# ArduinoMicroPrinter.net
KiCad netlist of a schematic drawn in EAGLE
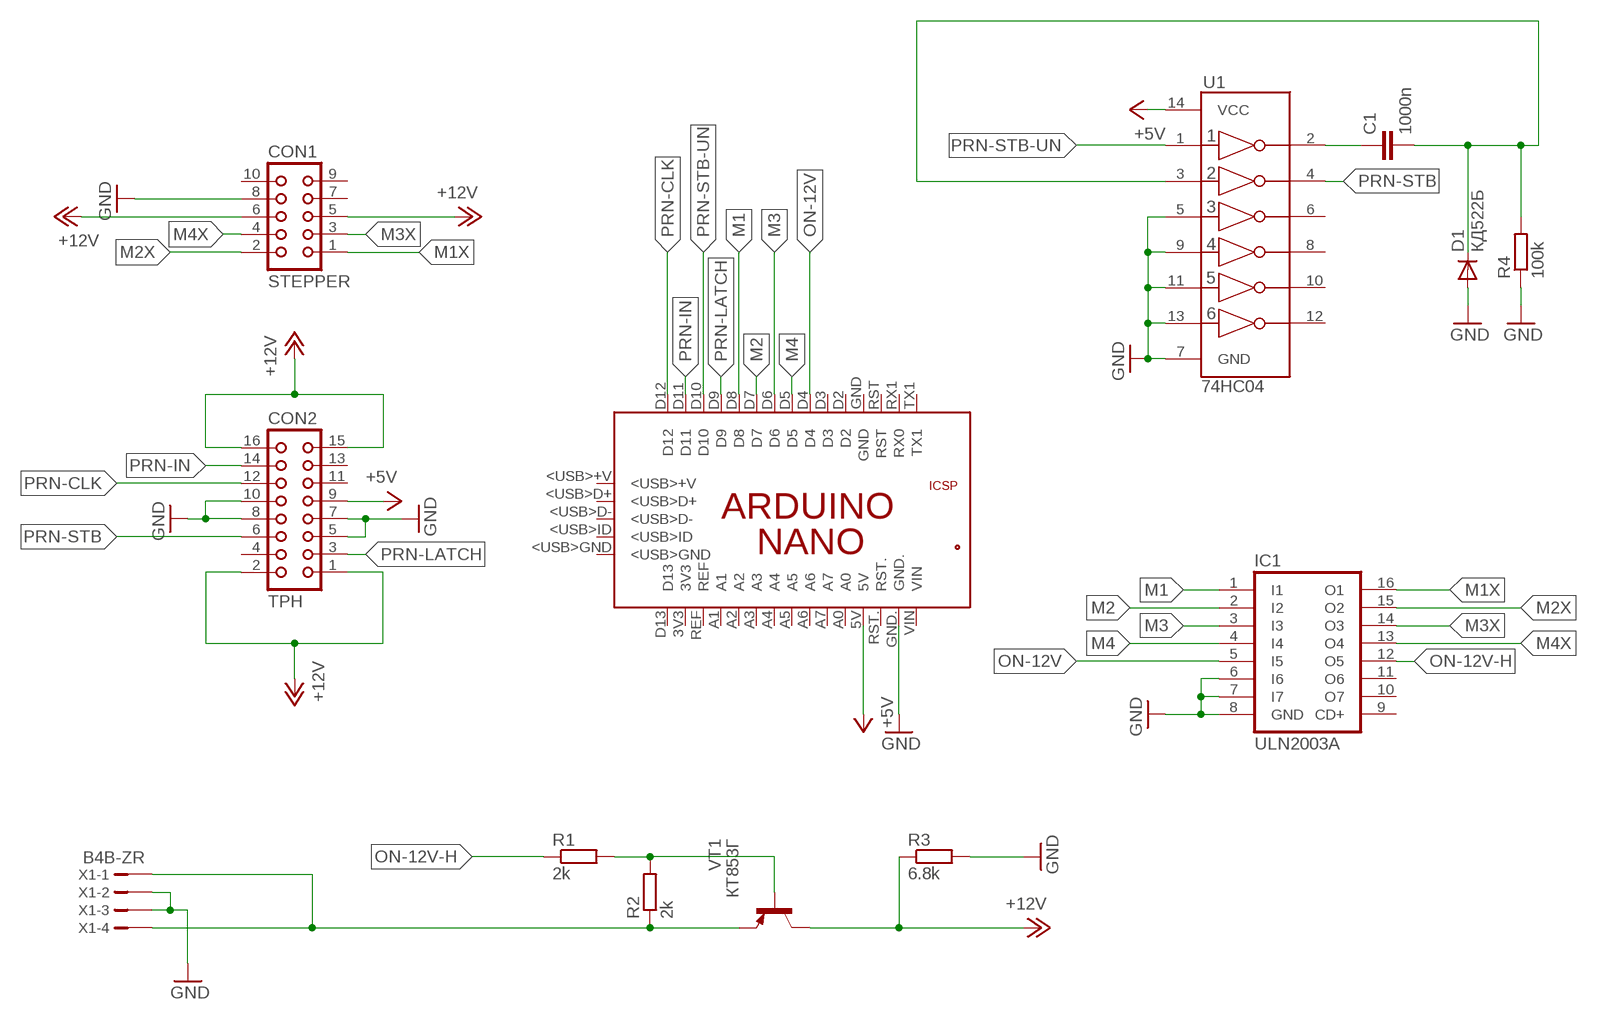
[diagram p0: schematic, sheet 1]

(export (version "E")
  (design (tool "Eeschema 10.0.6"))
  (components
    (comp (ref "C1")
      (value "1000n")
      (footprint "eagle-import:C075-032X103")
      (libsource (lib "eagle-import") (part "C-EU075-032X103"))
    )
    (comp (ref "CON1")
      (value "STEPPER")
      (footprint "eagle-import:CON10")
      (fields
        (field (name "MF") "TE CONNECTIVITY / AMP")
        (field (name "MPN") "0-281273-1")
        (field (name "OC_FARNELL") "3816278")
      )
      (libsource (lib "eagle-import") (part "CON10"))
    )
    (comp (ref "CON2")
      (value "TPH")
      (footprint "eagle-import:CON16")
      (fields
        (field (name "MF") "TE CONNECTIVITY / AMP")
        (field (name "MPN") "1-1634688-0")
        (field (name "OC_FARNELL") "8395918")
      )
      (libsource (lib "eagle-import") (part "CON16"))
    )
    (comp (ref "D1")
      (value "КД522Б")
      (footprint "eagle-import:DO35-10")
      (libsource (lib "eagle-import") (part "1N4148DO35-10"))
    )
    (comp (ref "IC1")
      (value "ULN2003A")
      (footprint "eagle-import:DIL16")
      (libsource (lib "eagle-import") (part "ULN2003AN"))
    )
    (comp (ref "PCB1")
      (value "ARDUINO_NANO")
      (footprint "eagle-import:ARDUINO_NANO")
      (fields (field (name "MF") "ARDUINO") (field (name "MPN") "A000005"))
      (libsource (lib "eagle-import") (part "ARDUINO_NANO"))
    )
    (comp (ref "R1")
      (value "2k")
      (footprint "eagle-import:0207_12")
      (libsource (lib "eagle-import") (part "R-EU_0207/12"))
    )
    (comp (ref "R2")
      (value "2k")
      (footprint "eagle-import:0207_12")
      (libsource (lib "eagle-import") (part "R-EU_0207/12"))
    )
    (comp (ref "R3")
      (value "6.8k")
      (footprint "eagle-import:0207_12")
      (libsource (lib "eagle-import") (part "R-EU_0207/12"))
    )
    (comp (ref "R4")
      (value "100k")
      (footprint "eagle-import:0309_12")
      (libsource (lib "eagle-import") (part "R-EU_0309/12"))
    )
    (comp (ref "U1")
      (value "74HC04")
      (footprint "eagle-import:DIL14")
      (libsource (lib "eagle-import") (part "74HC04_HEX_INVERTER"))
    )
    (comp (ref "VT1")
      (value "КТ853Г")
      (footprint "eagle-import:TO220")
      (libsource (lib "eagle-import") (part "TIP30"))
    )
    (comp (ref "X1")
      (value "B4B-ZR")
      (footprint "eagle-import:B4B-ZR")
      (fields (field (name "MF") "FARNELL") (field (name "MPN") "B4B-ZR(LF)(SN)"))
      (libsource (lib "eagle-import") (part "?4B-ZRB"))
    )
  )
  (nets
    (net (code "1") (name "+5V") (class "Default")
      (node (ref "CON2") (pin "9") (pinfunction "9_9") (pintype "passive"))
      (node (ref "PCB1") (pin "5V") (pinfunction "5V_5V") (pintype "bidirectional"))
      (node (ref "U1") (pin "14") (pinfunction "VCC_14") (pintype "power_in"))
    )
    (net (code "2") (name "+12V") (class "Default")
      (node (ref "CON1") (pin "5") (pinfunction "5_5") (pintype "passive"))
      (node (ref "CON1") (pin "6") (pinfunction "6_6") (pintype "passive"))
      (node (ref "CON2") (pin "1") (pinfunction "1_1") (pintype "passive"))
      (node (ref "CON2") (pin "15") (pinfunction "15_15") (pintype "passive"))
      (node (ref "CON2") (pin "16") (pinfunction "16_16") (pintype "passive"))
      (node (ref "CON2") (pin "2") (pinfunction "2_2") (pintype "passive"))
      (node (ref "R3") (pin "1") (pinfunction "1_1") (pintype "passive"))
      (node (ref "VT1") (pin "2") (pinfunction "C_2") (pintype "passive"))
    )
    (net (code "3") (name "GND") (class "Default")
      (node (ref "CON1") (pin "8") (pinfunction "8_8") (pintype "passive"))
      (node (ref "CON2") (pin "10") (pinfunction "10_10") (pintype "passive"))
      (node (ref "CON2") (pin "5") (pinfunction "5_5") (pintype "passive"))
      (node (ref "CON2") (pin "7") (pinfunction "7_7") (pintype "passive"))
      (node (ref "CON2") (pin "8") (pinfunction "8_8") (pintype "passive"))
      (node (ref "D1") (pin "A") (pinfunction "A_A") (pintype "passive"))
      (node (ref "IC1") (pin "6") (pinfunction "I6_6") (pintype "input"))
      (node (ref "IC1") (pin "7") (pinfunction "I7_7") (pintype "input"))
      (node (ref "IC1") (pin "8") (pinfunction "GND_8") (pintype "power_in"))
      (node (ref "PCB1") (pin "GND.") (pinfunction "GND._GND.") (pintype "bidirectional"))
      (node (ref "R3") (pin "2") (pinfunction "2_2") (pintype "passive"))
      (node (ref "R4") (pin "1") (pinfunction "1_1") (pintype "passive"))
      (node (ref "U1") (pin "11") (pinfunction "5A_11") (pintype "input"))
      (node (ref "U1") (pin "13") (pinfunction "6A_13") (pintype "input"))
      (node (ref "U1") (pin "5") (pinfunction "3A_5") (pintype "input"))
      (node (ref "U1") (pin "7") (pinfunction "GND_7") (pintype "power_in"))
      (node (ref "U1") (pin "9") (pinfunction "4A_9") (pintype "input"))
      (node (ref "X1") (pin "2") (pinfunction "1_2") (pintype "passive"))
      (node (ref "X1") (pin "3") (pinfunction "1_3") (pintype "passive"))
    )
    (net (code "4") (name "M1") (class "Default")
      (node (ref "IC1") (pin "1") (pinfunction "I1_1") (pintype "input"))
      (node (ref "PCB1") (pin "D8") (pinfunction "D8_D8") (pintype "bidirectional"))
    )
    (net (code "5") (name "M1X") (class "Default")
      (node (ref "CON1") (pin "1") (pinfunction "1_1") (pintype "passive"))
      (node (ref "IC1") (pin "16") (pinfunction "O1_16") (pintype "open_collector"))
    )
    (net (code "6") (name "M2") (class "Default")
      (node (ref "IC1") (pin "2") (pinfunction "I2_2") (pintype "input"))
      (node (ref "PCB1") (pin "D7") (pinfunction "D7_D7") (pintype "bidirectional"))
    )
    (net (code "7") (name "M2X") (class "Default")
      (node (ref "CON1") (pin "2") (pinfunction "2_2") (pintype "passive"))
      (node (ref "IC1") (pin "15") (pinfunction "O2_15") (pintype "open_collector"))
    )
    (net (code "8") (name "M3") (class "Default")
      (node (ref "IC1") (pin "3") (pinfunction "I3_3") (pintype "input"))
      (node (ref "PCB1") (pin "D6") (pinfunction "D6_D6") (pintype "bidirectional"))
    )
    (net (code "9") (name "M3X") (class "Default")
      (node (ref "CON1") (pin "3") (pinfunction "3_3") (pintype "passive"))
      (node (ref "IC1") (pin "14") (pinfunction "O3_14") (pintype "open_collector"))
    )
    (net (code "10") (name "M4") (class "Default")
      (node (ref "IC1") (pin "4") (pinfunction "I4_4") (pintype "input"))
      (node (ref "PCB1") (pin "D5") (pinfunction "D5_D5") (pintype "bidirectional"))
    )
    (net (code "11") (name "M4X") (class "Default")
      (node (ref "CON1") (pin "4") (pinfunction "4_4") (pintype "passive"))
      (node (ref "IC1") (pin "13") (pinfunction "O4_13") (pintype "open_collector"))
    )
    (net (code "12") (name "Net-(U1-1Y)") (class "Default")
      (node (ref "C1") (pin "1") (pinfunction "1_1") (pintype "passive"))
      (node (ref "U1") (pin "2") (pinfunction "1Y_2") (pintype "output"))
    )
    (net (code "13") (name "Net-(U1-2A)") (class "Default")
      (node (ref "C1") (pin "2") (pinfunction "2_2") (pintype "passive"))
      (node (ref "D1") (pin "C") (pinfunction "C_C") (pintype "passive"))
      (node (ref "R4") (pin "2") (pinfunction "2_2") (pintype "passive"))
      (node (ref "U1") (pin "3") (pinfunction "2A_3") (pintype "input"))
    )
    (net (code "14") (name "Net-(VT1-B)") (class "Default")
      (node (ref "R1") (pin "2") (pinfunction "2_2") (pintype "passive"))
      (node (ref "R2") (pin "2") (pinfunction "2_2") (pintype "passive"))
      (node (ref "VT1") (pin "1") (pinfunction "B_1") (pintype "passive"))
    )
    (net (code "15") (name "Net-(VT1-E)") (class "Default")
      (node (ref "R2") (pin "1") (pinfunction "1_1") (pintype "passive"))
      (node (ref "VT1") (pin "3") (pinfunction "E_3") (pintype "passive"))
      (node (ref "X1") (pin "1") (pinfunction "1_1") (pintype "passive"))
      (node (ref "X1") (pin "4") (pinfunction "1_4") (pintype "passive"))
    )
    (net (code "16") (name "ON-12V") (class "Default")
      (node (ref "IC1") (pin "5") (pinfunction "I5_5") (pintype "input"))
      (node (ref "PCB1") (pin "D4") (pinfunction "D4_D4") (pintype "bidirectional"))
    )
    (net (code "17") (name "ON-12V-H") (class "Default")
      (node (ref "IC1") (pin "12") (pinfunction "O5_12") (pintype "open_collector"))
      (node (ref "R1") (pin "1") (pinfunction "1_1") (pintype "passive"))
    )
    (net (code "18") (name "PRN-CLK") (class "Default")
      (node (ref "CON2") (pin "12") (pinfunction "12_12") (pintype "passive"))
      (node (ref "PCB1") (pin "D12") (pinfunction "D12_D12") (pintype "bidirectional"))
    )
    (net (code "19") (name "PRN-IN") (class "Default")
      (node (ref "CON2") (pin "14") (pinfunction "14_14") (pintype "passive"))
      (node (ref "PCB1") (pin "D11") (pinfunction "D11_D11") (pintype "bidirectional"))
    )
    (net (code "20") (name "PRN-LATCH") (class "Default")
      (node (ref "CON2") (pin "3") (pinfunction "3_3") (pintype "passive"))
      (node (ref "PCB1") (pin "D9") (pinfunction "D9_D9") (pintype "bidirectional"))
    )
    (net (code "21") (name "PRN-STB") (class "Default")
      (node (ref "CON2") (pin "6") (pinfunction "6_6") (pintype "passive"))
      (node (ref "U1") (pin "4") (pinfunction "2Y_4") (pintype "output"))
    )
    (net (code "22") (name "PRN-STB-UN") (class "Default")
      (node (ref "PCB1") (pin "D10") (pinfunction "D10_D10") (pintype "bidirectional"))
      (node (ref "U1") (pin "1") (pinfunction "1A_1") (pintype "input"))
    )
    (net (code "23") (name "unconnected-(CON1-Pad7)") (class "Default")
      (node (ref "CON1") (pin "7") (pinfunction "7_7") (pintype "passive"))
    )
    (net (code "24") (name "unconnected-(CON1-Pad9)") (class "Default")
      (node (ref "CON1") (pin "9") (pinfunction "9_9") (pintype "passive"))
    )
    (net (code "25") (name "unconnected-(CON1-Pad10)") (class "Default")
      (node (ref "CON1") (pin "10") (pinfunction "10_10") (pintype "passive"))
    )
    (net (code "26") (name "unconnected-(CON2-Pad4)") (class "Default")
      (node (ref "CON2") (pin "4") (pinfunction "4_4") (pintype "passive"))
    )
    (net (code "27") (name "unconnected-(CON2-Pad11)") (class "Default")
      (node (ref "CON2") (pin "11") (pinfunction "11_11") (pintype "passive"))
    )
    (net (code "28") (name "unconnected-(CON2-Pad13)") (class "Default")
      (node (ref "CON2") (pin "13") (pinfunction "13_13") (pintype "passive"))
    )
    (net (code "29") (name "unconnected-(IC1-CD+-Pad9)") (class "Default")
      (node (ref "IC1") (pin "9") (pinfunction "CD+_9") (pintype "passive"))
    )
    (net (code "30") (name "unconnected-(IC1-O6-Pad11)") (class "Default")
      (node (ref "IC1") (pin "11") (pinfunction "O6_11") (pintype "open_collector"))
    )
    (net (code "31") (name "unconnected-(IC1-O7-Pad10)") (class "Default")
      (node (ref "IC1") (pin "10") (pinfunction "O7_10") (pintype "open_collector"))
    )
    (net (code "32") (name "unconnected-(PCB1-Pad3V3)") (class "Default")
      (node (ref "PCB1") (pin "3V3") (pinfunction "3V3_3V3") (pintype "bidirectional"))
    )
    (net (code "33") (name "unconnected-(PCB1-Pad5V.)") (class "Default")
      (node (ref "PCB1") (pin "5V.") (pinfunction "5V._5V.") (pintype "bidirectional"))
    )
    (net (code "34") (name "unconnected-(PCB1-Pad<USB>+V)") (class "Default")
      (node (ref "PCB1") (pin "<USB>+V") (pinfunction "<USB>+V_<USB>+V") (pintype "bidirectional"))
    )
    (net (code "35") (name "unconnected-(PCB1-Pad<USB>D+)") (class "Default")
      (node (ref "PCB1") (pin "<USB>D+") (pinfunction "<USB>D+_<USB>D+") (pintype "bidirectional"))
    )
    (net (code "36") (name "unconnected-(PCB1-Pad<USB>D-)") (class "Default")
      (node (ref "PCB1") (pin "<USB>D-") (pinfunction "<USB>D-_<USB>D-") (pintype "bidirectional"))
    )
    (net (code "37") (name "unconnected-(PCB1-Pad<USB>GND)") (class "Default")
      (node (ref "PCB1") (pin "<USB>GND") (pinfunction "<USB>GND_<USB>GND") (pintype "bidirectional"))
    )
    (net (code "38") (name "unconnected-(PCB1-Pad<USB>ID)") (class "Default")
      (node (ref "PCB1") (pin "<USB>ID") (pinfunction "<USB>ID_<USB>ID") (pintype "bidirectional"))
    )
    (net (code "39") (name "unconnected-(PCB1-PadA0)") (class "Default")
      (node (ref "PCB1") (pin "A0") (pinfunction "A0_A0") (pintype "bidirectional"))
    )
    (net (code "40") (name "unconnected-(PCB1-PadA1)") (class "Default")
      (node (ref "PCB1") (pin "A1") (pinfunction "A1_A1") (pintype "bidirectional"))
    )
    (net (code "41") (name "unconnected-(PCB1-PadA2)") (class "Default")
      (node (ref "PCB1") (pin "A2") (pinfunction "A2_A2") (pintype "bidirectional"))
    )
    (net (code "42") (name "unconnected-(PCB1-PadA3)") (class "Default")
      (node (ref "PCB1") (pin "A3") (pinfunction "A3_A3") (pintype "bidirectional"))
    )
    (net (code "43") (name "unconnected-(PCB1-PadA4)") (class "Default")
      (node (ref "PCB1") (pin "A4") (pinfunction "A4_A4") (pintype "bidirectional"))
    )
    (net (code "44") (name "unconnected-(PCB1-PadA5)") (class "Default")
      (node (ref "PCB1") (pin "A5") (pinfunction "A5_A5") (pintype "bidirectional"))
    )
    (net (code "45") (name "unconnected-(PCB1-PadA6)") (class "Default")
      (node (ref "PCB1") (pin "A6") (pinfunction "A6_A6") (pintype "bidirectional"))
    )
    (net (code "46") (name "unconnected-(PCB1-PadA7)") (class "Default")
      (node (ref "PCB1") (pin "A7") (pinfunction "A7_A7") (pintype "bidirectional"))
    )
    (net (code "47") (name "unconnected-(PCB1-PadD2)") (class "Default")
      (node (ref "PCB1") (pin "D2") (pinfunction "D2_D2") (pintype "bidirectional"))
    )
    (net (code "48") (name "unconnected-(PCB1-PadD3)") (class "Default")
      (node (ref "PCB1") (pin "D3") (pinfunction "D3_D3") (pintype "bidirectional"))
    )
    (net (code "49") (name "unconnected-(PCB1-PadD13)") (class "Default")
      (node (ref "PCB1") (pin "D13") (pinfunction "D13_D13") (pintype "bidirectional"))
    )
    (net (code "50") (name "unconnected-(PCB1-PadGND)") (class "Default")
      (node (ref "PCB1") (pin "GND") (pinfunction "GND_GND") (pintype "bidirectional"))
    )
    (net (code "51") (name "unconnected-(PCB1-PadGND_)") (class "Default")
      (node (ref "PCB1") (pin "GND_") (pinfunction "GND__GND_") (pintype "bidirectional"))
    )
    (net (code "52") (name "unconnected-(PCB1-PadMISO)") (class "Default")
      (node (ref "PCB1") (pin "MISO") (pinfunction "MISO_MISO") (pintype "bidirectional"))
    )
    (net (code "53") (name "unconnected-(PCB1-PadMOSI)") (class "Default")
      (node (ref "PCB1") (pin "MOSI") (pinfunction "MOSI_MOSI") (pintype "bidirectional"))
    )
    (net (code "54") (name "unconnected-(PCB1-PadREF)") (class "Default")
      (node (ref "PCB1") (pin "REF") (pinfunction "REF_REF") (pintype "bidirectional"))
    )
    (net (code "55") (name "unconnected-(PCB1-PadRESET..)") (class "Default")
      (node (ref "PCB1") (pin "RESET..") (pinfunction "RESET.._RESET..") (pintype "bidirectional"))
    )
    (net (code "56") (name "unconnected-(PCB1-PadRST)") (class "Default")
      (node (ref "PCB1") (pin "RST") (pinfunction "RST_RST") (pintype "bidirectional"))
    )
    (net (code "57") (name "unconnected-(PCB1-PadRST.)") (class "Default")
      (node (ref "PCB1") (pin "RST.") (pinfunction "RST._RST.") (pintype "bidirectional"))
    )
    (net (code "58") (name "unconnected-(PCB1-PadSCK)") (class "Default")
      (node (ref "PCB1") (pin "SCK") (pinfunction "SCK_SCK") (pintype "bidirectional"))
    )
    (net (code "59") (name "unconnected-(PCB1-PadTX1)") (class "Default")
      (node (ref "PCB1") (pin "TX1") (pinfunction "TX1_TX1") (pintype "bidirectional"))
    )
    (net (code "60") (name "unconnected-(PCB1-PadVIN)") (class "Default")
      (node (ref "PCB1") (pin "VIN") (pinfunction "VIN_VIN") (pintype "bidirectional"))
    )
    (net (code "61") (name "unconnected-(PCB1-RX0-PadRX1)") (class "Default")
      (node (ref "PCB1") (pin "RX1") (pinfunction "RX0_RX1") (pintype "bidirectional"))
    )
    (net (code "62") (name "unconnected-(U1-3Y-Pad6)") (class "Default")
      (node (ref "U1") (pin "6") (pinfunction "3Y_6") (pintype "output"))
    )
    (net (code "63") (name "unconnected-(U1-4Y-Pad8)") (class "Default")
      (node (ref "U1") (pin "8") (pinfunction "4Y_8") (pintype "output"))
    )
    (net (code "64") (name "unconnected-(U1-5Y-Pad10)") (class "Default")
      (node (ref "U1") (pin "10") (pinfunction "5Y_10") (pintype "output"))
    )
    (net (code "65") (name "unconnected-(U1-6Y-Pad12)") (class "Default")
      (node (ref "U1") (pin "12") (pinfunction "6Y_12") (pintype "output"))
    )
  )
)
